# pitching_v1.net
KiCad netlist of a schematic drawn in EAGLE
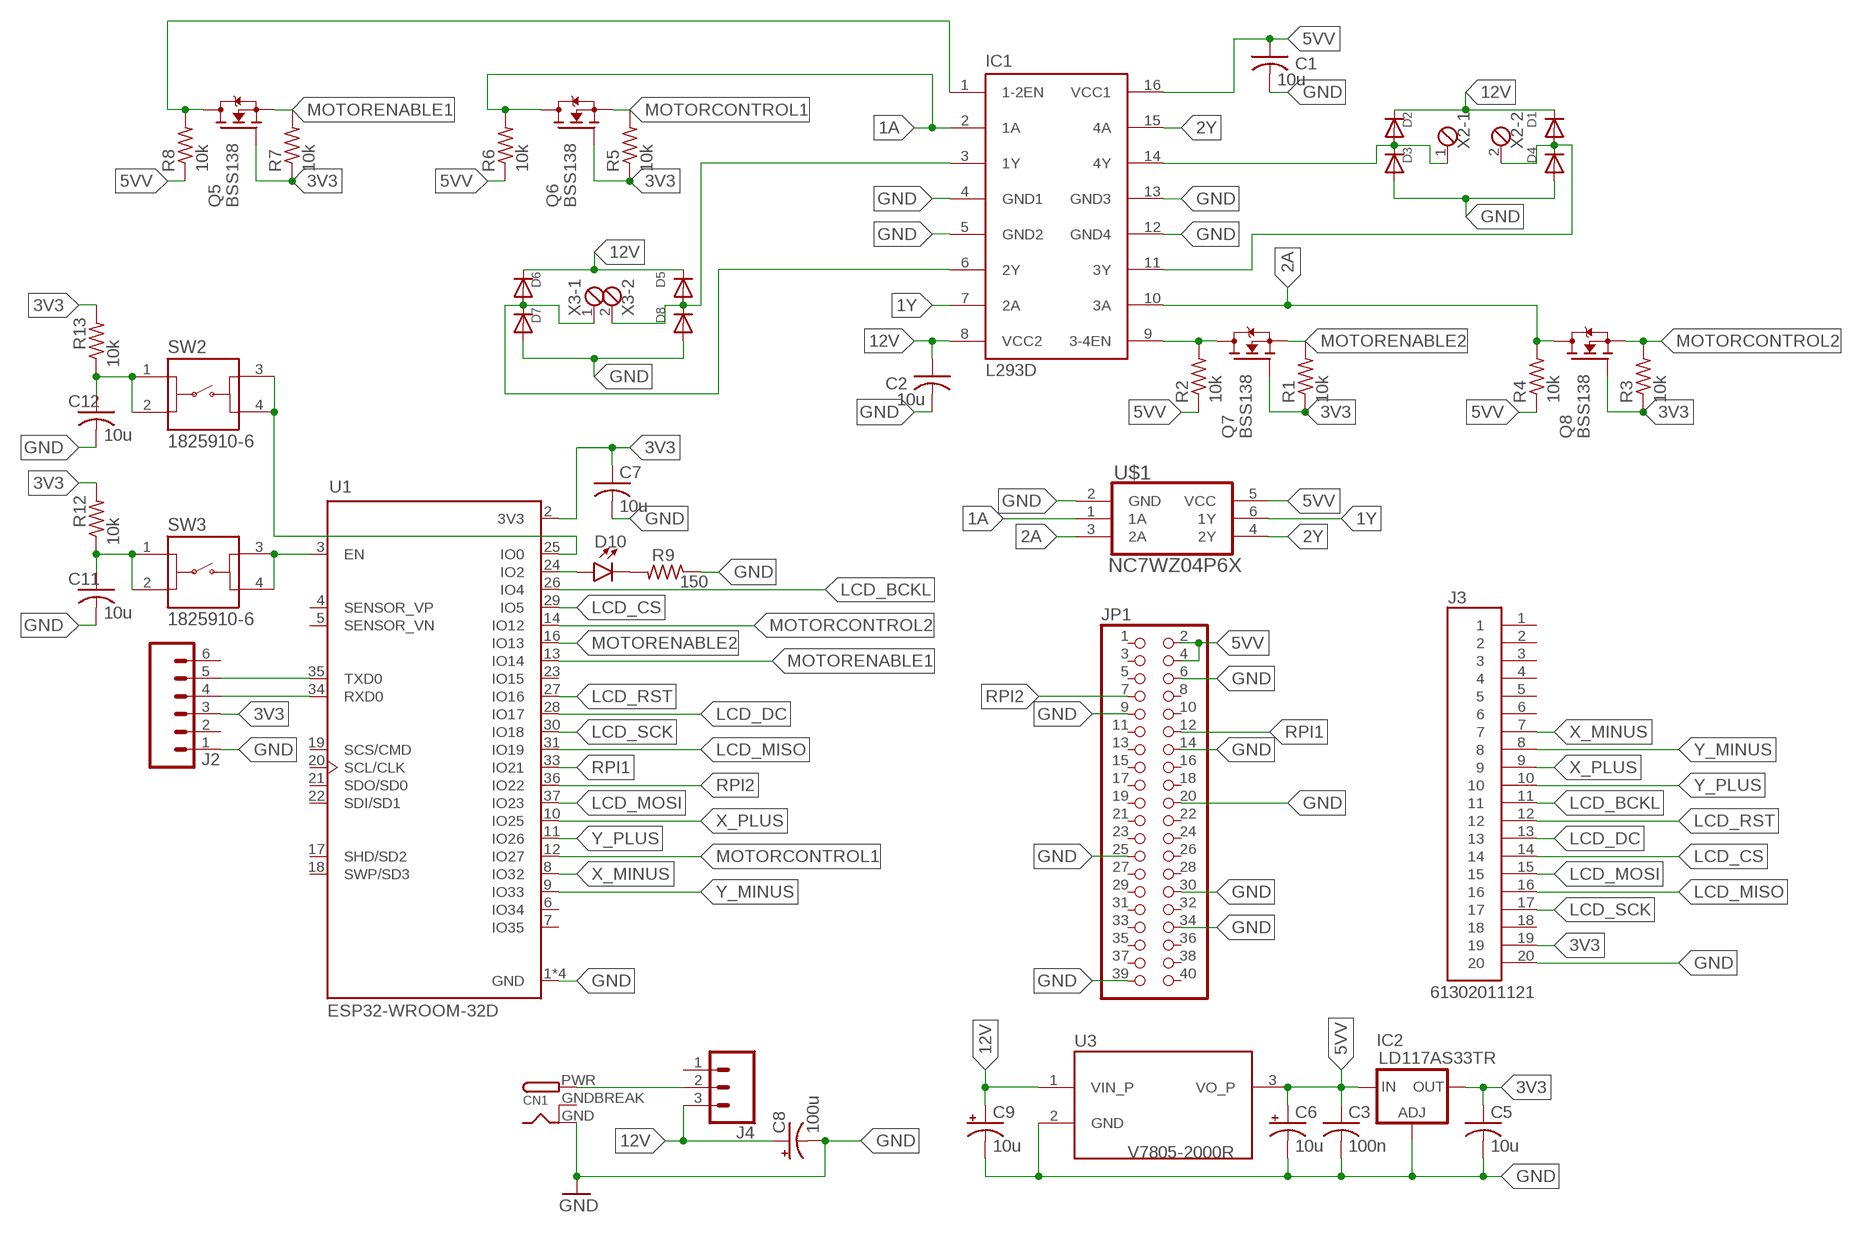
[diagram p0: schematic, sheet 1]

(export (version "E")
  (design (tool "Eeschema 10.0.6"))
  (components
    (comp (ref "C1")
      (value "10u")
      (footprint "eagle-import:C0805")
      (libsource (lib "eagle-import") (part "C-USC0805"))
    )
    (comp (ref "C2")
      (value "10u")
      (footprint "eagle-import:C0805")
      (libsource (lib "eagle-import") (part "C-USC0805"))
    )
    (comp (ref "C3")
      (value "100n")
      (footprint "eagle-import:C0805")
      (libsource (lib "eagle-import") (part "C-USC0805"))
    )
    (comp (ref "C5")
      (value "10u")
      (footprint "eagle-import:C0805")
      (libsource (lib "eagle-import") (part "C-USC0805"))
    )
    (comp (ref "C6")
      (value "10u")
      (footprint "eagle-import:153CLV-0405")
      (libsource (lib "eagle-import") (part "CPOL-US153CLV-0405"))
    )
    (comp (ref "C7")
      (value "10u")
      (footprint "eagle-import:C0805")
      (libsource (lib "eagle-import") (part "C-USC0805"))
    )
    (comp (ref "C8")
      (value "100u")
      (footprint "eagle-import:153CLV-0810")
      (libsource (lib "eagle-import") (part "CPOL-US153CLV-0810"))
    )
    (comp (ref "C9")
      (value "10u")
      (footprint "eagle-import:153CLV-0405")
      (libsource (lib "eagle-import") (part "CPOL-US153CLV-0405"))
    )
    (comp (ref "C11")
      (value "10u")
      (footprint "eagle-import:C0805")
      (libsource (lib "eagle-import") (part "C-USC0805"))
    )
    (comp (ref "C12")
      (value "10u")
      (footprint "eagle-import:C0805")
      (libsource (lib "eagle-import") (part "C-USC0805"))
    )
    (comp (ref "CN1")
      (value "DCBARRELPTH")
      (footprint "eagle-import:DCJACK_2MM_PTH")
      (libsource (lib "eagle-import") (part "DCBARRELPTH"))
    )
    (comp (ref "D1")
      (value "DIODESMA")
      (footprint "eagle-import:SMADIODE")
      (libsource (lib "eagle-import") (part "DIODESMA"))
    )
    (comp (ref "D2")
      (value "DIODESMA")
      (footprint "eagle-import:SMADIODE")
      (libsource (lib "eagle-import") (part "DIODESMA"))
    )
    (comp (ref "D3")
      (value "DIODESMA")
      (footprint "eagle-import:SMADIODE")
      (libsource (lib "eagle-import") (part "DIODESMA"))
    )
    (comp (ref "D4")
      (value "DIODESMA")
      (footprint "eagle-import:SMADIODE")
      (libsource (lib "eagle-import") (part "DIODESMA"))
    )
    (comp (ref "D5")
      (value "DIODESMA")
      (footprint "eagle-import:SMADIODE")
      (libsource (lib "eagle-import") (part "DIODESMA"))
    )
    (comp (ref "D6")
      (value "DIODESMA")
      (footprint "eagle-import:SMADIODE")
      (libsource (lib "eagle-import") (part "DIODESMA"))
    )
    (comp (ref "D7")
      (value "DIODESMA")
      (footprint "eagle-import:SMADIODE")
      (libsource (lib "eagle-import") (part "DIODESMA"))
    )
    (comp (ref "D8")
      (value "DIODESMA")
      (footprint "eagle-import:SMADIODE")
      (libsource (lib "eagle-import") (part "DIODESMA"))
    )
    (comp (ref "D10")
      (value "LED3MM")
      (footprint "eagle-import:LED_3MM")
      (libsource (lib "eagle-import") (part "LED3MM"))
    )
    (comp (ref "IC1")
      (value "L293D")
      (footprint "eagle-import:DIL16")
      (libsource (lib "eagle-import") (part "L293D"))
    )
    (comp (ref "IC2")
      (value "LD117AS33TR")
      (footprint "eagle-import:SOT223")
      (libsource (lib "eagle-import") (part "LD117A?S33TR"))
    )
    (comp (ref "J2")
      (value "CONN_06NO_SILK_FEMALE_PTH")
      (footprint "eagle-import:1X06_NO_SILK")
      (libsource (lib "eagle-import") (part "CONN_06NO_SILK_FEMALE_PTH"))
    )
    (comp (ref "J3")
      (value "61302011121")
      (footprint "eagle-import:61302011121")
      (fields
        (field (name "DIGIKEY_PART_NUMBER") "732-5329-ND")
        (field (name "MANUFACTURER") "Wurth Electronics Inc.")
        (field (name "CREATED_BY") "PCBLayout.com")
      )
      (libsource (lib "eagle-import") (part "61302011121"))
    )
    (comp (ref "J4")
      (value "CONN_03")
      (footprint "eagle-import:1X03")
      (libsource (lib "eagle-import") (part "CONN_03"))
    )
    (comp (ref "JP1")
      (value "PINHD-2X20")
      (footprint "eagle-import:2X20")
      (libsource (lib "eagle-import") (part "PINHD-2X20"))
    )
    (comp (ref "Q5")
      (value "BSS138")
      (footprint "eagle-import:SOT23")
      (fields (field (name "MF") "Fairchild"))
      (libsource (lib "eagle-import") (part "BSS138"))
    )
    (comp (ref "Q6")
      (value "BSS138")
      (footprint "eagle-import:SOT23")
      (fields (field (name "MF") "Fairchild"))
      (libsource (lib "eagle-import") (part "BSS138"))
    )
    (comp (ref "Q7")
      (value "BSS138")
      (footprint "eagle-import:SOT23")
      (fields (field (name "MF") "Fairchild"))
      (libsource (lib "eagle-import") (part "BSS138"))
    )
    (comp (ref "Q8")
      (value "BSS138")
      (footprint "eagle-import:SOT23")
      (fields (field (name "MF") "Fairchild"))
      (libsource (lib "eagle-import") (part "BSS138"))
    )
    (comp (ref "R1")
      (value "10k")
      (footprint "eagle-import:R0805")
      (libsource (lib "eagle-import") (part "R-US_R0805"))
    )
    (comp (ref "R2")
      (value "10k")
      (footprint "eagle-import:R0805")
      (libsource (lib "eagle-import") (part "R-US_R0805"))
    )
    (comp (ref "R3")
      (value "10k")
      (footprint "eagle-import:R0805")
      (libsource (lib "eagle-import") (part "R-US_R0805"))
    )
    (comp (ref "R4")
      (value "10k")
      (footprint "eagle-import:R0805")
      (libsource (lib "eagle-import") (part "R-US_R0805"))
    )
    (comp (ref "R5")
      (value "10k")
      (footprint "eagle-import:R0805")
      (libsource (lib "eagle-import") (part "R-US_R0805"))
    )
    (comp (ref "R6")
      (value "10k")
      (footprint "eagle-import:R0805")
      (libsource (lib "eagle-import") (part "R-US_R0805"))
    )
    (comp (ref "R7")
      (value "10k")
      (footprint "eagle-import:R0805")
      (libsource (lib "eagle-import") (part "R-US_R0805"))
    )
    (comp (ref "R8")
      (value "10k")
      (footprint "eagle-import:R0805")
      (libsource (lib "eagle-import") (part "R-US_R0805"))
    )
    (comp (ref "R9")
      (value "150")
      (footprint "eagle-import:R0805")
      (libsource (lib "eagle-import") (part "R-US_R0805"))
    )
    (comp (ref "R12")
      (value "10k")
      (footprint "eagle-import:R0805")
      (libsource (lib "eagle-import") (part "R-US_R0805"))
    )
    (comp (ref "R13")
      (value "10k")
      (footprint "eagle-import:R0805")
      (libsource (lib "eagle-import") (part "R-US_R0805"))
    )
    (comp (ref "SW2")
      (value "1825910-6")
      (footprint "eagle-import:1825910-6")
      (fields
        (field (name "DIGIKEY_PART_NUMBER") "450-1650-ND")
        (field (name "MANUFACTURER") "TE Connectivity ALCOSWITCH Switches")
        (field (name "CREATED_BY") " PCBLayout.com")
      )
      (libsource (lib "eagle-import") (part "1825910-6"))
    )
    (comp (ref "SW3")
      (value "1825910-6")
      (footprint "eagle-import:1825910-6")
      (fields
        (field (name "DIGIKEY_PART_NUMBER") "450-1650-ND")
        (field (name "MANUFACTURER") "TE Connectivity ALCOSWITCH Switches")
        (field (name "CREATED_BY") " PCBLayout.com")
      )
      (libsource (lib "eagle-import") (part "1825910-6"))
    )
    (comp (ref "U$1")
      (value "NC7WZ04P6X")
      (footprint "eagle-import:SOT65P210X110-6N")
      (libsource (lib "eagle-import") (part "NC7WZ04P6X"))
    )
    (comp (ref "U1")
      (value "ESP32-WROOM-32D")
      (footprint "eagle-import:MODULE_ESP32-WROOM-32D")
      (fields (field (name "MF") "Espressif Systems"))
      (libsource (lib "eagle-import") (part "ESP32-WROOM-32D"))
    )
    (comp (ref "U3")
      (value "V7805-2000R")
      (footprint "eagle-import:CONV_V7805-2000R")
      (fields (field (name "MANUFACTURER") "CUI INC"))
      (libsource (lib "eagle-import") (part "V7805-2000R"))
    )
    (comp (ref "X2")
      (value "MPT2")
      (footprint "eagle-import:2POL254")
      (libsource (lib "eagle-import") (part "MPT2"))
    )
    (comp (ref "X3")
      (value "MPT2")
      (footprint "eagle-import:2POL254")
      (libsource (lib "eagle-import") (part "MPT2"))
    )
  )
  (nets
    (net (code "1") (name "/GNDBREAK") (class "Default")
      (node (ref "CN1") (pin "GNDBREAK") (pinfunction "GNDBREAK_GNDBREAK") (pintype "power_in"))
    )
    (net (code "2") (name "1A") (class "Default")
      (node (ref "IC1") (pin "2") (pinfunction "1A_2") (pintype "input"))
      (node (ref "Q6") (pin "3") (pinfunction "D_3") (pintype "passive"))
      (node (ref "R6") (pin "2") (pinfunction "2_2") (pintype "passive"))
      (node (ref "U$1") (pin "1") (pinfunction "1A_1") (pintype "passive"))
    )
    (net (code "3") (name "1Y") (class "Default")
      (node (ref "IC1") (pin "7") (pinfunction "2A_7") (pintype "input"))
      (node (ref "U$1") (pin "6") (pinfunction "1Y_6") (pintype "passive"))
    )
    (net (code "4") (name "2A") (class "Default")
      (node (ref "IC1") (pin "10") (pinfunction "3A_10") (pintype "input"))
      (node (ref "Q8") (pin "3") (pinfunction "D_3") (pintype "passive"))
      (node (ref "R4") (pin "2") (pinfunction "2_2") (pintype "passive"))
      (node (ref "U$1") (pin "3") (pinfunction "2A_3") (pintype "passive"))
    )
    (net (code "5") (name "2Y") (class "Default")
      (node (ref "IC1") (pin "15") (pinfunction "4A_15") (pintype "input"))
      (node (ref "U$1") (pin "4") (pinfunction "2Y_4") (pintype "passive"))
    )
    (net (code "6") (name "3V3") (class "Default")
      (node (ref "C5") (pin "1") (pinfunction "1_1") (pintype "passive"))
      (node (ref "C7") (pin "1") (pinfunction "1_1") (pintype "passive"))
      (node (ref "IC2") (pin "4") (pinfunction "OUT_4") (pintype "passive"))
      (node (ref "J2") (pin "3") (pinfunction "3_3") (pintype "passive"))
      (node (ref "J3") (pin "19") (pinfunction "19_19") (pintype "passive"))
      (node (ref "Q5") (pin "1") (pinfunction "G_1") (pintype "passive"))
      (node (ref "Q6") (pin "1") (pinfunction "G_1") (pintype "passive"))
      (node (ref "Q7") (pin "1") (pinfunction "G_1") (pintype "passive"))
      (node (ref "Q8") (pin "1") (pinfunction "G_1") (pintype "passive"))
      (node (ref "R1") (pin "1") (pinfunction "1_1") (pintype "passive"))
      (node (ref "R12") (pin "2") (pinfunction "2_2") (pintype "passive"))
      (node (ref "R13") (pin "2") (pinfunction "2_2") (pintype "passive"))
      (node (ref "R3") (pin "1") (pinfunction "1_1") (pintype "passive"))
      (node (ref "R5") (pin "1") (pinfunction "1_1") (pintype "passive"))
      (node (ref "R7") (pin "1") (pinfunction "1_1") (pintype "passive"))
      (node (ref "U1") (pin "2") (pinfunction "3V3_2") (pintype "power_in"))
    )
    (net (code "7") (name "5VV") (class "Default")
      (node (ref "C1") (pin "1") (pinfunction "1_1") (pintype "passive"))
      (node (ref "C3") (pin "1") (pinfunction "1_1") (pintype "passive"))
      (node (ref "C6") (pin "+") (pinfunction "+_+") (pintype "passive"))
      (node (ref "IC1") (pin "16") (pinfunction "VCC1_16") (pintype "power_in"))
      (node (ref "IC2") (pin "3") (pinfunction "IN_3") (pintype "input"))
      (node (ref "JP1") (pin "2") (pinfunction "2_2") (pintype "passive"))
      (node (ref "JP1") (pin "4") (pinfunction "4_4") (pintype "passive"))
      (node (ref "R2") (pin "1") (pinfunction "1_1") (pintype "passive"))
      (node (ref "R4") (pin "1") (pinfunction "1_1") (pintype "passive"))
      (node (ref "R6") (pin "1") (pinfunction "1_1") (pintype "passive"))
      (node (ref "R8") (pin "1") (pinfunction "1_1") (pintype "passive"))
      (node (ref "U$1") (pin "5") (pinfunction "VCC_5") (pintype "passive"))
      (node (ref "U3") (pin "3") (pinfunction "VO_P_3") (pintype "output"))
    )
    (net (code "8") (name "12V") (class "Default")
      (node (ref "C2") (pin "1") (pinfunction "1_1") (pintype "passive"))
      (node (ref "C8") (pin "+") (pinfunction "+_+") (pintype "passive"))
      (node (ref "C9") (pin "+") (pinfunction "+_+") (pintype "passive"))
      (node (ref "D1") (pin "C") (pinfunction "C_C") (pintype "passive"))
      (node (ref "D2") (pin "C") (pinfunction "C_C") (pintype "passive"))
      (node (ref "D5") (pin "C") (pinfunction "C_C") (pintype "passive"))
      (node (ref "D6") (pin "C") (pinfunction "C_C") (pintype "passive"))
      (node (ref "IC1") (pin "8") (pinfunction "VCC2_8") (pintype "power_in"))
      (node (ref "J4") (pin "3") (pinfunction "3_3") (pintype "passive"))
      (node (ref "U3") (pin "1") (pinfunction "VIN_P_1") (pintype "input"))
    )
    (net (code "9") (name "GND") (class "Default")
      (node (ref "C1") (pin "2") (pinfunction "2_2") (pintype "passive"))
      (node (ref "C11") (pin "2") (pinfunction "2_2") (pintype "passive"))
      (node (ref "C12") (pin "2") (pinfunction "2_2") (pintype "passive"))
      (node (ref "C2") (pin "2") (pinfunction "2_2") (pintype "passive"))
      (node (ref "C3") (pin "2") (pinfunction "2_2") (pintype "passive"))
      (node (ref "C5") (pin "2") (pinfunction "2_2") (pintype "passive"))
      (node (ref "C6") (pin "-") (pinfunction "-_-") (pintype "passive"))
      (node (ref "C7") (pin "2") (pinfunction "2_2") (pintype "passive"))
      (node (ref "C8") (pin "-") (pinfunction "-_-") (pintype "passive"))
      (node (ref "C9") (pin "-") (pinfunction "-_-") (pintype "passive"))
      (node (ref "CN1") (pin "GND") (pinfunction "GND_GND") (pintype "power_in"))
      (node (ref "D3") (pin "A") (pinfunction "A_A") (pintype "passive"))
      (node (ref "D4") (pin "A") (pinfunction "A_A") (pintype "passive"))
      (node (ref "D7") (pin "A") (pinfunction "A_A") (pintype "passive"))
      (node (ref "D8") (pin "A") (pinfunction "A_A") (pintype "passive"))
      (node (ref "IC1") (pin "12") (pinfunction "GND4_12") (pintype "power_in"))
      (node (ref "IC1") (pin "13") (pinfunction "GND3_13") (pintype "power_in"))
      (node (ref "IC1") (pin "4") (pinfunction "GND1_4") (pintype "power_in"))
      (node (ref "IC1") (pin "5") (pinfunction "GND2_5") (pintype "power_in"))
      (node (ref "IC2") (pin "1") (pinfunction "ADJ_1") (pintype "input"))
      (node (ref "J2") (pin "1") (pinfunction "1_1") (pintype "passive"))
      (node (ref "J3") (pin "20") (pinfunction "20_20") (pintype "passive"))
      (node (ref "JP1") (pin "14") (pinfunction "14_14") (pintype "passive"))
      (node (ref "JP1") (pin "20") (pinfunction "20_20") (pintype "passive"))
      (node (ref "JP1") (pin "25") (pinfunction "25_25") (pintype "passive"))
      (node (ref "JP1") (pin "30") (pinfunction "30_30") (pintype "passive"))
      (node (ref "JP1") (pin "34") (pinfunction "34_34") (pintype "passive"))
      (node (ref "JP1") (pin "39") (pinfunction "39_39") (pintype "passive"))
      (node (ref "JP1") (pin "6") (pinfunction "6_6") (pintype "passive"))
      (node (ref "JP1") (pin "9") (pinfunction "9_9") (pintype "passive"))
      (node (ref "R9") (pin "1") (pinfunction "1_1") (pintype "passive"))
      (node (ref "U$1") (pin "2") (pinfunction "GND_2") (pintype "passive"))
      (node (ref "U1") (pin "1") (pinfunction "GND_1") (pintype "power_in"))
      (node (ref "U1") (pin "15") (pinfunction "GND_15") (pintype "power_in"))
      (node (ref "U1") (pin "38") (pinfunction "GND_38") (pintype "power_in"))
      (node (ref "U1") (pin "39") (pinfunction "GND_39") (pintype "power_in"))
      (node (ref "U3") (pin "2") (pinfunction "GND_2") (pintype "power_in"))
    )
    (net (code "10") (name "LCD_BCKL") (class "Default")
      (node (ref "J3") (pin "11") (pinfunction "11_11") (pintype "passive"))
      (node (ref "U1") (pin "26") (pinfunction "IO4_26") (pintype "bidirectional"))
    )
    (net (code "11") (name "LCD_CS") (class "Default")
      (node (ref "J3") (pin "14") (pinfunction "14_14") (pintype "passive"))
      (node (ref "U1") (pin "29") (pinfunction "IO5_29") (pintype "bidirectional"))
    )
    (net (code "12") (name "LCD_DC") (class "Default")
      (node (ref "J3") (pin "13") (pinfunction "13_13") (pintype "passive"))
      (node (ref "U1") (pin "28") (pinfunction "IO17_28") (pintype "bidirectional"))
    )
    (net (code "13") (name "LCD_MISO") (class "Default")
      (node (ref "J3") (pin "16") (pinfunction "16_16") (pintype "passive"))
      (node (ref "U1") (pin "31") (pinfunction "IO19_31") (pintype "bidirectional"))
    )
    (net (code "14") (name "LCD_MOSI") (class "Default")
      (node (ref "J3") (pin "15") (pinfunction "15_15") (pintype "passive"))
      (node (ref "U1") (pin "37") (pinfunction "IO23_37") (pintype "bidirectional"))
    )
    (net (code "15") (name "LCD_RST") (class "Default")
      (node (ref "J3") (pin "12") (pinfunction "12_12") (pintype "passive"))
      (node (ref "U1") (pin "27") (pinfunction "IO16_27") (pintype "bidirectional"))
    )
    (net (code "16") (name "LCD_SCK") (class "Default")
      (node (ref "J3") (pin "17") (pinfunction "17_17") (pintype "passive"))
      (node (ref "U1") (pin "30") (pinfunction "IO18_30") (pintype "bidirectional"))
    )
    (net (code "17") (name "MOTORCONTROL1") (class "Default")
      (node (ref "Q6") (pin "2") (pinfunction "S_2") (pintype "passive"))
      (node (ref "R5") (pin "2") (pinfunction "2_2") (pintype "passive"))
      (node (ref "U1") (pin "12") (pinfunction "IO27_12") (pintype "bidirectional"))
    )
    (net (code "18") (name "MOTORCONTROL2") (class "Default")
      (node (ref "Q8") (pin "2") (pinfunction "S_2") (pintype "passive"))
      (node (ref "R3") (pin "2") (pinfunction "2_2") (pintype "passive"))
      (node (ref "U1") (pin "14") (pinfunction "IO12_14") (pintype "bidirectional"))
    )
    (net (code "19") (name "MOTORENABLE1") (class "Default")
      (node (ref "Q5") (pin "2") (pinfunction "S_2") (pintype "passive"))
      (node (ref "R7") (pin "2") (pinfunction "2_2") (pintype "passive"))
      (node (ref "U1") (pin "13") (pinfunction "IO14_13") (pintype "bidirectional"))
    )
    (net (code "20") (name "MOTORENABLE2") (class "Default")
      (node (ref "Q7") (pin "2") (pinfunction "S_2") (pintype "passive"))
      (node (ref "R1") (pin "2") (pinfunction "2_2") (pintype "passive"))
      (node (ref "U1") (pin "16") (pinfunction "IO13_16") (pintype "bidirectional"))
    )
    (net (code "21") (name "Net-(C11-Pad1)") (class "Default")
      (node (ref "C11") (pin "1") (pinfunction "1_1") (pintype "passive"))
      (node (ref "R12") (pin "1") (pinfunction "1_1") (pintype "passive"))
      (node (ref "SW3") (pin "1") (pinfunction "1_1") (pintype "passive"))
      (node (ref "SW3") (pin "2") (pinfunction "2_2") (pintype "passive"))
    )
    (net (code "22") (name "Net-(C12-Pad1)") (class "Default")
      (node (ref "C12") (pin "1") (pinfunction "1_1") (pintype "passive"))
      (node (ref "R13") (pin "1") (pinfunction "1_1") (pintype "passive"))
      (node (ref "SW2") (pin "1") (pinfunction "1_1") (pintype "passive"))
      (node (ref "SW2") (pin "2") (pinfunction "2_2") (pintype "passive"))
    )
    (net (code "23") (name "Net-(CN1-PadPWR)") (class "Default")
      (node (ref "CN1") (pin "PWR") (pinfunction "PWR_PWR") (pintype "power_in"))
      (node (ref "J4") (pin "2") (pinfunction "2_2") (pintype "passive"))
    )
    (net (code "24") (name "Net-(D10-C)") (class "Default")
      (node (ref "D10") (pin "K") (pinfunction "C_K") (pintype "passive"))
      (node (ref "R9") (pin "2") (pinfunction "2_2") (pintype "passive"))
    )
    (net (code "25") (name "Net-(IC1-1-2EN)") (class "Default")
      (node (ref "IC1") (pin "1") (pinfunction "1-2EN_1") (pintype "input"))
      (node (ref "Q5") (pin "3") (pinfunction "D_3") (pintype "passive"))
      (node (ref "R8") (pin "2") (pinfunction "2_2") (pintype "passive"))
    )
    (net (code "26") (name "Net-(IC1-1Y)") (class "Default")
      (node (ref "D5") (pin "A") (pinfunction "A_A") (pintype "passive"))
      (node (ref "D8") (pin "C") (pinfunction "C_C") (pintype "passive"))
      (node (ref "IC1") (pin "3") (pinfunction "1Y_3") (pintype "output"))
      (node (ref "X3") (pin "2") (pinfunction "1_2") (pintype "passive"))
    )
    (net (code "27") (name "Net-(IC1-2Y)") (class "Default")
      (node (ref "D6") (pin "A") (pinfunction "A_A") (pintype "passive"))
      (node (ref "D7") (pin "C") (pinfunction "C_C") (pintype "passive"))
      (node (ref "IC1") (pin "6") (pinfunction "2Y_6") (pintype "output"))
      (node (ref "X3") (pin "1") (pinfunction "1_1") (pintype "passive"))
    )
    (net (code "28") (name "Net-(IC1-3-4EN)") (class "Default")
      (node (ref "IC1") (pin "9") (pinfunction "3-4EN_9") (pintype "input"))
      (node (ref "Q7") (pin "3") (pinfunction "D_3") (pintype "passive"))
      (node (ref "R2") (pin "2") (pinfunction "2_2") (pintype "passive"))
    )
    (net (code "29") (name "Net-(IC1-3Y)") (class "Default")
      (node (ref "D1") (pin "A") (pinfunction "A_A") (pintype "passive"))
      (node (ref "D4") (pin "C") (pinfunction "C_C") (pintype "passive"))
      (node (ref "IC1") (pin "11") (pinfunction "3Y_11") (pintype "output"))
      (node (ref "X2") (pin "2") (pinfunction "1_2") (pintype "passive"))
    )
    (net (code "30") (name "Net-(IC1-4Y)") (class "Default")
      (node (ref "D2") (pin "A") (pinfunction "A_A") (pintype "passive"))
      (node (ref "D3") (pin "C") (pinfunction "C_C") (pintype "passive"))
      (node (ref "IC1") (pin "14") (pinfunction "4Y_14") (pintype "output"))
      (node (ref "X2") (pin "1") (pinfunction "1_1") (pintype "passive"))
    )
    (net (code "31") (name "Net-(U1-EN)") (class "Default")
      (node (ref "SW3") (pin "3") (pinfunction "3_3") (pintype "passive"))
      (node (ref "SW3") (pin "4") (pinfunction "4_4") (pintype "passive"))
      (node (ref "U1") (pin "3") (pinfunction "EN_3") (pintype "input"))
    )
    (net (code "32") (name "Net-(U1-IO0)") (class "Default")
      (node (ref "SW2") (pin "3") (pinfunction "3_3") (pintype "passive"))
      (node (ref "SW2") (pin "4") (pinfunction "4_4") (pintype "passive"))
      (node (ref "U1") (pin "25") (pinfunction "IO0_25") (pintype "bidirectional"))
    )
    (net (code "33") (name "Net-(U1-IO2)") (class "Default")
      (node (ref "D10") (pin "A") (pinfunction "A_A") (pintype "passive"))
      (node (ref "U1") (pin "24") (pinfunction "IO2_24") (pintype "bidirectional"))
    )
    (net (code "34") (name "Net-(U1-RXD0)") (class "Default")
      (node (ref "J2") (pin "4") (pinfunction "4_4") (pintype "passive"))
      (node (ref "U1") (pin "34") (pinfunction "RXD0_34") (pintype "bidirectional"))
    )
    (net (code "35") (name "Net-(U1-TXD0)") (class "Default")
      (node (ref "J2") (pin "5") (pinfunction "5_5") (pintype "passive"))
      (node (ref "U1") (pin "35") (pinfunction "TXD0_35") (pintype "bidirectional"))
    )
    (net (code "36") (name "RPI1") (class "Default")
      (node (ref "JP1") (pin "12") (pinfunction "12_12") (pintype "passive"))
      (node (ref "U1") (pin "33") (pinfunction "IO21_33") (pintype "bidirectional"))
    )
    (net (code "37") (name "RPI2") (class "Default")
      (node (ref "JP1") (pin "7") (pinfunction "7_7") (pintype "passive"))
      (node (ref "U1") (pin "36") (pinfunction "IO22_36") (pintype "bidirectional"))
    )
    (net (code "38") (name "X_MINUS") (class "Default")
      (node (ref "J3") (pin "7") (pinfunction "7_7") (pintype "passive"))
      (node (ref "U1") (pin "8") (pinfunction "IO32_8") (pintype "bidirectional"))
    )
    (net (code "39") (name "X_PLUS") (class "Default")
      (node (ref "J3") (pin "9") (pinfunction "9_9") (pintype "passive"))
      (node (ref "U1") (pin "10") (pinfunction "IO25_10") (pintype "bidirectional"))
    )
    (net (code "40") (name "Y_MINUS") (class "Default")
      (node (ref "J3") (pin "8") (pinfunction "8_8") (pintype "passive"))
      (node (ref "U1") (pin "9") (pinfunction "IO33_9") (pintype "bidirectional"))
    )
    (net (code "41") (name "Y_PLUS") (class "Default")
      (node (ref "J3") (pin "10") (pinfunction "10_10") (pintype "passive"))
      (node (ref "U1") (pin "11") (pinfunction "IO26_11") (pintype "bidirectional"))
    )
    (net (code "42") (name "unconnected-(J2-Pad2)") (class "Default")
      (node (ref "J2") (pin "2") (pinfunction "2_2") (pintype "passive"))
    )
    (net (code "43") (name "unconnected-(J2-Pad6)") (class "Default")
      (node (ref "J2") (pin "6") (pinfunction "6_6") (pintype "passive"))
    )
    (net (code "44") (name "unconnected-(J3-Pad1)") (class "Default")
      (node (ref "J3") (pin "1") (pinfunction "1_1") (pintype "passive"))
    )
    (net (code "45") (name "unconnected-(J3-Pad2)") (class "Default")
      (node (ref "J3") (pin "2") (pinfunction "2_2") (pintype "passive"))
    )
    (net (code "46") (name "unconnected-(J3-Pad3)") (class "Default")
      (node (ref "J3") (pin "3") (pinfunction "3_3") (pintype "passive"))
    )
    (net (code "47") (name "unconnected-(J3-Pad4)") (class "Default")
      (node (ref "J3") (pin "4") (pinfunction "4_4") (pintype "passive"))
    )
    (net (code "48") (name "unconnected-(J3-Pad5)") (class "Default")
      (node (ref "J3") (pin "5") (pinfunction "5_5") (pintype "passive"))
    )
    (net (code "49") (name "unconnected-(J3-Pad6)") (class "Default")
      (node (ref "J3") (pin "6") (pinfunction "6_6") (pintype "passive"))
    )
    (net (code "50") (name "unconnected-(J3-Pad18)") (class "Default")
      (node (ref "J3") (pin "18") (pinfunction "18_18") (pintype "passive"))
    )
    (net (code "51") (name "unconnected-(J4-Pad1)") (class "Default")
      (node (ref "J4") (pin "1") (pinfunction "1_1") (pintype "passive"))
    )
    (net (code "52") (name "unconnected-(JP1-Pad1)") (class "Default")
      (node (ref "JP1") (pin "1") (pinfunction "1_1") (pintype "passive"))
    )
    (net (code "53") (name "unconnected-(JP1-Pad3)") (class "Default")
      (node (ref "JP1") (pin "3") (pinfunction "3_3") (pintype "passive"))
    )
    (net (code "54") (name "unconnected-(JP1-Pad5)") (class "Default")
      (node (ref "JP1") (pin "5") (pinfunction "5_5") (pintype "passive"))
    )
    (net (code "55") (name "unconnected-(JP1-Pad8)") (class "Default")
      (node (ref "JP1") (pin "8") (pinfunction "8_8") (pintype "passive"))
    )
    (net (code "56") (name "unconnected-(JP1-Pad10)") (class "Default")
      (node (ref "JP1") (pin "10") (pinfunction "10_10") (pintype "passive"))
    )
    (net (code "57") (name "unconnected-(JP1-Pad11)") (class "Default")
      (node (ref "JP1") (pin "11") (pinfunction "11_11") (pintype "passive"))
    )
    (net (code "58") (name "unconnected-(JP1-Pad13)") (class "Default")
      (node (ref "JP1") (pin "13") (pinfunction "13_13") (pintype "passive"))
    )
    (net (code "59") (name "unconnected-(JP1-Pad15)") (class "Default")
      (node (ref "JP1") (pin "15") (pinfunction "15_15") (pintype "passive"))
    )
    (net (code "60") (name "unconnected-(JP1-Pad16)") (class "Default")
      (node (ref "JP1") (pin "16") (pinfunction "16_16") (pintype "passive"))
    )
    (net (code "61") (name "unconnected-(JP1-Pad17)") (class "Default")
      (node (ref "JP1") (pin "17") (pinfunction "17_17") (pintype "passive"))
    )
    (net (code "62") (name "unconnected-(JP1-Pad18)") (class "Default")
      (node (ref "JP1") (pin "18") (pinfunction "18_18") (pintype "passive"))
    )
    (net (code "63") (name "unconnected-(JP1-Pad19)") (class "Default")
      (node (ref "JP1") (pin "19") (pinfunction "19_19") (pintype "passive"))
    )
    (net (code "64") (name "unconnected-(JP1-Pad21)") (class "Default")
      (node (ref "JP1") (pin "21") (pinfunction "21_21") (pintype "passive"))
    )
    (net (code "65") (name "unconnected-(JP1-Pad22)") (class "Default")
      (node (ref "JP1") (pin "22") (pinfunction "22_22") (pintype "passive"))
    )
    (net (code "66") (name "unconnected-(JP1-Pad23)") (class "Default")
      (node (ref "JP1") (pin "23") (pinfunction "23_23") (pintype "passive"))
    )
    (net (code "67") (name "unconnected-(JP1-Pad24)") (class "Default")
      (node (ref "JP1") (pin "24") (pinfunction "24_24") (pintype "passive"))
    )
    (net (code "68") (name "unconnected-(JP1-Pad26)") (class "Default")
      (node (ref "JP1") (pin "26") (pinfunction "26_26") (pintype "passive"))
    )
    (net (code "69") (name "unconnected-(JP1-Pad27)") (class "Default")
      (node (ref "JP1") (pin "27") (pinfunction "27_27") (pintype "passive"))
    )
    (net (code "70") (name "unconnected-(JP1-Pad28)") (class "Default")
      (node (ref "JP1") (pin "28") (pinfunction "28_28") (pintype "passive"))
    )
    (net (code "71") (name "unconnected-(JP1-Pad29)") (class "Default")
      (node (ref "JP1") (pin "29") (pinfunction "29_29") (pintype "passive"))
    )
    (net (code "72") (name "unconnected-(JP1-Pad31)") (class "Default")
      (node (ref "JP1") (pin "31") (pinfunction "31_31") (pintype "passive"))
    )
    (net (code "73") (name "unconnected-(JP1-Pad32)") (class "Default")
      (node (ref "JP1") (pin "32") (pinfunction "32_32") (pintype "passive"))
    )
    (net (code "74") (name "unconnected-(JP1-Pad33)") (class "Default")
      (node (ref "JP1") (pin "33") (pinfunction "33_33") (pintype "passive"))
    )
    (net (code "75") (name "unconnected-(JP1-Pad35)") (class "Default")
      (node (ref "JP1") (pin "35") (pinfunction "35_35") (pintype "passive"))
    )
    (net (code "76") (name "unconnected-(JP1-Pad36)") (class "Default")
      (node (ref "JP1") (pin "36") (pinfunction "36_36") (pintype "passive"))
    )
    (net (code "77") (name "unconnected-(JP1-Pad37)") (class "Default")
      (node (ref "JP1") (pin "37") (pinfunction "37_37") (pintype "passive"))
    )
    (net (code "78") (name "unconnected-(JP1-Pad38)") (class "Default")
      (node (ref "JP1") (pin "38") (pinfunction "38_38") (pintype "passive"))
    )
    (net (code "79") (name "unconnected-(JP1-Pad40)") (class "Default")
      (node (ref "JP1") (pin "40") (pinfunction "40_40") (pintype "passive"))
    )
    (net (code "80") (name "unconnected-(U1-IO15-Pad23)") (class "Default")
      (node (ref "U1") (pin "23") (pinfunction "IO15_23") (pintype "bidirectional"))
    )
    (net (code "81") (name "unconnected-(U1-IO34-Pad6)") (class "Default")
      (node (ref "U1") (pin "6") (pinfunction "IO34_6") (pintype "bidirectional"))
    )
    (net (code "82") (name "unconnected-(U1-IO35-Pad7)") (class "Default")
      (node (ref "U1") (pin "7") (pinfunction "IO35_7") (pintype "bidirectional"))
    )
    (net (code "83") (name "unconnected-(U1-SCL{slash}CLK-Pad20)") (class "Default")
      (node (ref "U1") (pin "20") (pinfunction "SCL/CLK_20") (pintype "bidirectional"))
    )
    (net (code "84") (name "unconnected-(U1-SCS{slash}CMD-Pad19)") (class "Default")
      (node (ref "U1") (pin "19") (pinfunction "SCS/CMD_19") (pintype "bidirectional"))
    )
    (net (code "85") (name "unconnected-(U1-SDI{slash}SD1-Pad22)") (class "Default")
      (node (ref "U1") (pin "22") (pinfunction "SDI/SD1_22") (pintype "bidirectional"))
    )
    (net (code "86") (name "unconnected-(U1-SDO{slash}SD0-Pad21)") (class "Default")
      (node (ref "U1") (pin "21") (pinfunction "SDO/SD0_21") (pintype "bidirectional"))
    )
    (net (code "87") (name "unconnected-(U1-SENSOR_VN-Pad5)") (class "Default")
      (node (ref "U1") (pin "5") (pinfunction "SENSOR_VN_5") (pintype "input"))
    )
    (net (code "88") (name "unconnected-(U1-SENSOR_VP-Pad4)") (class "Default")
      (node (ref "U1") (pin "4") (pinfunction "SENSOR_VP_4") (pintype "input"))
    )
    (net (code "89") (name "unconnected-(U1-SHD{slash}SD2-Pad17)") (class "Default")
      (node (ref "U1") (pin "17") (pinfunction "SHD/SD2_17") (pintype "bidirectional"))
    )
    (net (code "90") (name "unconnected-(U1-SWP{slash}SD3-Pad18)") (class "Default")
      (node (ref "U1") (pin "18") (pinfunction "SWP/SD3_18") (pintype "bidirectional"))
    )
  )
)
